# PWR.net
KiCad netlist of a schematic drawn in Altium Designer
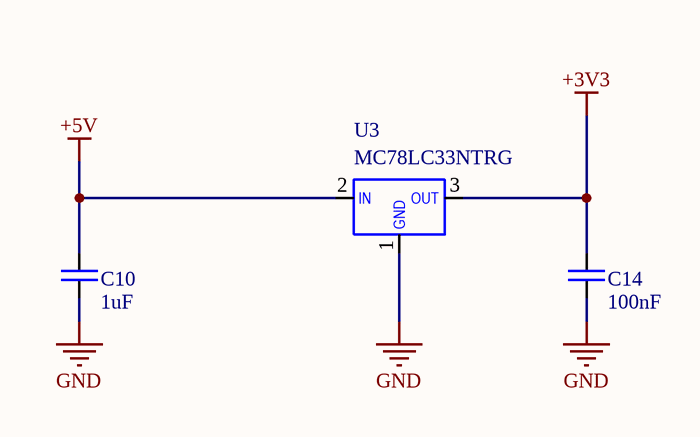
[diagram p0: PWR.SchDoc]

(export (version "E")
  (design (tool "Eeschema 10.0.6"))
  (components
    (comp (ref "C10")
      (value "1uF")
      (footprint "DISCRETE:SMD_0805")
      (description "None polar capacitor")
      (libsource (lib "DISCRETE") (part "C_NONE_POLAR"))
    )
    (comp (ref "C14")
      (value "100nF")
      (footprint "DISCRETE:SMD_0805")
      (description "None polar capacitor")
      (libsource (lib "DISCRETE") (part "C_NONE_POLAR"))
    )
    (comp (ref "U3")
      (value "MC78LC33NTRG")
      (footprint "ICs:SOT753")
      (description "Low dropout Linear Voltage Regulator")
      (libsource (lib "ICs") (part "MC78LC33NTRG"))
    )
  )
  (nets
    (net (code "1") (name "+3V3") (class "Default")
      (node (ref "C14") (pin "1") (pintype "passive"))
      (node (ref "U3") (pin "3") (pinfunction "OUT_3") (pintype "power_in"))
    )
    (net (code "2") (name "+5V") (class "Default")
      (node (ref "C10") (pin "1") (pintype "passive"))
      (node (ref "U3") (pin "2") (pinfunction "IN_2") (pintype "power_in"))
    )
    (net (code "3") (name "GND") (class "Default")
      (node (ref "C10") (pin "2") (pintype "passive"))
      (node (ref "C14") (pin "2") (pintype "passive"))
      (node (ref "U3") (pin "1") (pinfunction "GND_1") (pintype "passive"))
    )
  )
)
